# Interface_RS485.net
KiCad netlist of a schematic drawn in Altium Designer
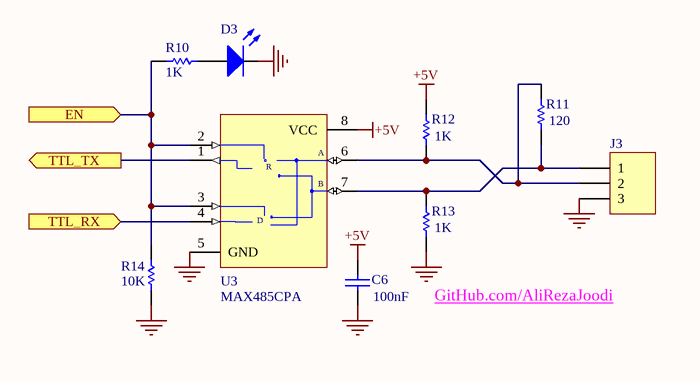
[diagram p0: Interface_RS485.SchDoc]

(export (version "E")
  (design (tool "Eeschema 10.0.6"))
  (components
    (comp (ref "C6")
      (value "100nF")
      (footprint "CAPNTO2.54-3.05x1.78A")
      (description "Capacitor")
      (fields (field (name "Comment") "Cap") (field (name "PUBLISHER") "Altium Limited"))
      (libsource (lib "Miscellaneous Devices") (part "Cap"))
    )
    (comp (ref "D3")
      (value "LED")
      (footprint "LED-5mm_Red")
      (description "Typical INFRARED GaAs LED")
      (fields (field (name "MANUFACTURER") "Generic Components") (field (name "PUBLISHER") "Altium Limited"))
      (libsource (lib "Miscellaneous Devices") (part "LED"))
    )
    (comp (ref "J3")
      (value "Header 3")
      (footprint "Fonics_3PIN_1")
      (description "Header, 3-Pin")
      (fields (field (name "MANUFACTURER") "Generic Components") (field (name "PUBLISHER") "Altium Limited"))
      (libsource (lib "Miscellaneous Connectors") (part "Header 3"))
    )
    (comp (ref "R10")
      (value "1K")
      (footprint "AXIAL-0.4")
      (description "Resistor")
      (fields (field (name "MANUFACTURER") "Generic Components") (field (name "PUBLISHER") "Altium Limited"))
      (libsource (lib "Miscellaneous Devices") (part "Res1"))
    )
    (comp (ref "R11")
      (value "120")
      (footprint "AXIAL-0.4")
      (description "Resistor")
      (fields (field (name "Comment") "Res1") (field (name "PUBLISHER") "Altium Limited"))
      (libsource (lib "Miscellaneous Devices") (part "Res1"))
    )
    (comp (ref "R12")
      (value "1K")
      (footprint "AXIAL-0.4")
      (description "Resistor")
      (fields (field (name "Comment") "Res1") (field (name "PUBLISHER") "Altium Limited"))
      (libsource (lib "Miscellaneous Devices") (part "Res1"))
    )
    (comp (ref "R13")
      (value "1K")
      (footprint "AXIAL-0.4")
      (description "Resistor")
      (fields (field (name "Comment") "Res1") (field (name "PUBLISHER") "Altium Limited"))
      (libsource (lib "Miscellaneous Devices") (part "Res1"))
    )
    (comp (ref "R14")
      (value "10K")
      (footprint "AXIAL-0.4")
      (description "Resistor")
      (fields (field (name "Comment") "Res1") (field (name "PUBLISHER") "Altium Limited"))
      (libsource (lib "Miscellaneous Devices") (part "Res1"))
    )
    (comp (ref "U3")
      (value "MAX485CPA")
      (footprint "PA8")
      (description "Low-Power, Slew-Rate-Limited RS-485/RS-422 Transceiver")
      (fields (field (name "PUBLISHER") "Altium Limited"))
      (libsource (lib "Maxim Communication Transceiver") (part "MAX485CPA"))
    )
  )
  (nets
    (net (code "1") (name "+5V") (class "Default")
      (node (ref "C6") (pin "1") (pinfunction "1_1") (pintype "passive"))
      (node (ref "R12") (pin "1") (pinfunction "1_1") (pintype "passive"))
      (node (ref "U3") (pin "8") (pinfunction "VCC_8") (pintype "power_in"))
    )
    (net (code "2") (name "/EN") (class "Default")
      (node (ref "R10") (pin "2") (pinfunction "2_2") (pintype "passive"))
      (node (ref "R14") (pin "2") (pinfunction "2_2") (pintype "passive"))
      (node (ref "U3") (pin "2") (pinfunction "~{RE}_2") (pintype "input"))
      (node (ref "U3") (pin "3") (pinfunction "DE_3") (pintype "input"))
    )
    (net (code "3") (name "/TTL_RX") (class "Default")
      (node (ref "U3") (pin "4") (pinfunction "DI_4") (pintype "input"))
    )
    (net (code "4") (name "/TTL_TX") (class "Default")
      (node (ref "U3") (pin "1") (pinfunction "RO_1") (pintype "output"))
    )
    (net (code "5") (name "GND") (class "Default")
      (node (ref "C6") (pin "2") (pinfunction "2_2") (pintype "passive"))
      (node (ref "D3") (pin "2") (pinfunction "K_2") (pintype "passive"))
      (node (ref "J3") (pin "3") (pinfunction "3_3") (pintype "passive"))
      (node (ref "R13") (pin "2") (pinfunction "2_2") (pintype "passive"))
      (node (ref "R14") (pin "1") (pinfunction "1_1") (pintype "passive"))
      (node (ref "U3") (pin "5") (pinfunction "GND_5") (pintype "power_in"))
    )
    (net (code "6") (name "Net-(D3-A)") (class "Default")
      (node (ref "D3") (pin "1") (pinfunction "A_1") (pintype "passive"))
      (node (ref "R10") (pin "1") (pinfunction "1_1") (pintype "passive"))
    )
    (net (code "7") (name "Net-(U3-A)") (class "Default")
      (node (ref "J3") (pin "2") (pinfunction "2_2") (pintype "passive"))
      (node (ref "R11") (pin "1") (pinfunction "1_1") (pintype "passive"))
      (node (ref "R12") (pin "2") (pinfunction "2_2") (pintype "passive"))
      (node (ref "U3") (pin "6") (pinfunction "A_6") (pintype "bidirectional"))
    )
    (net (code "8") (name "Net-(U3-B)") (class "Default")
      (node (ref "J3") (pin "1") (pinfunction "1_1") (pintype "passive"))
      (node (ref "R11") (pin "2") (pinfunction "2_2") (pintype "passive"))
      (node (ref "R13") (pin "1") (pinfunction "1_1") (pintype "passive"))
      (node (ref "U3") (pin "7") (pinfunction "B_7") (pintype "bidirectional"))
    )
  )
)
